# gpio4.net
KiCad netlist of a schematic drawn in EAGLE
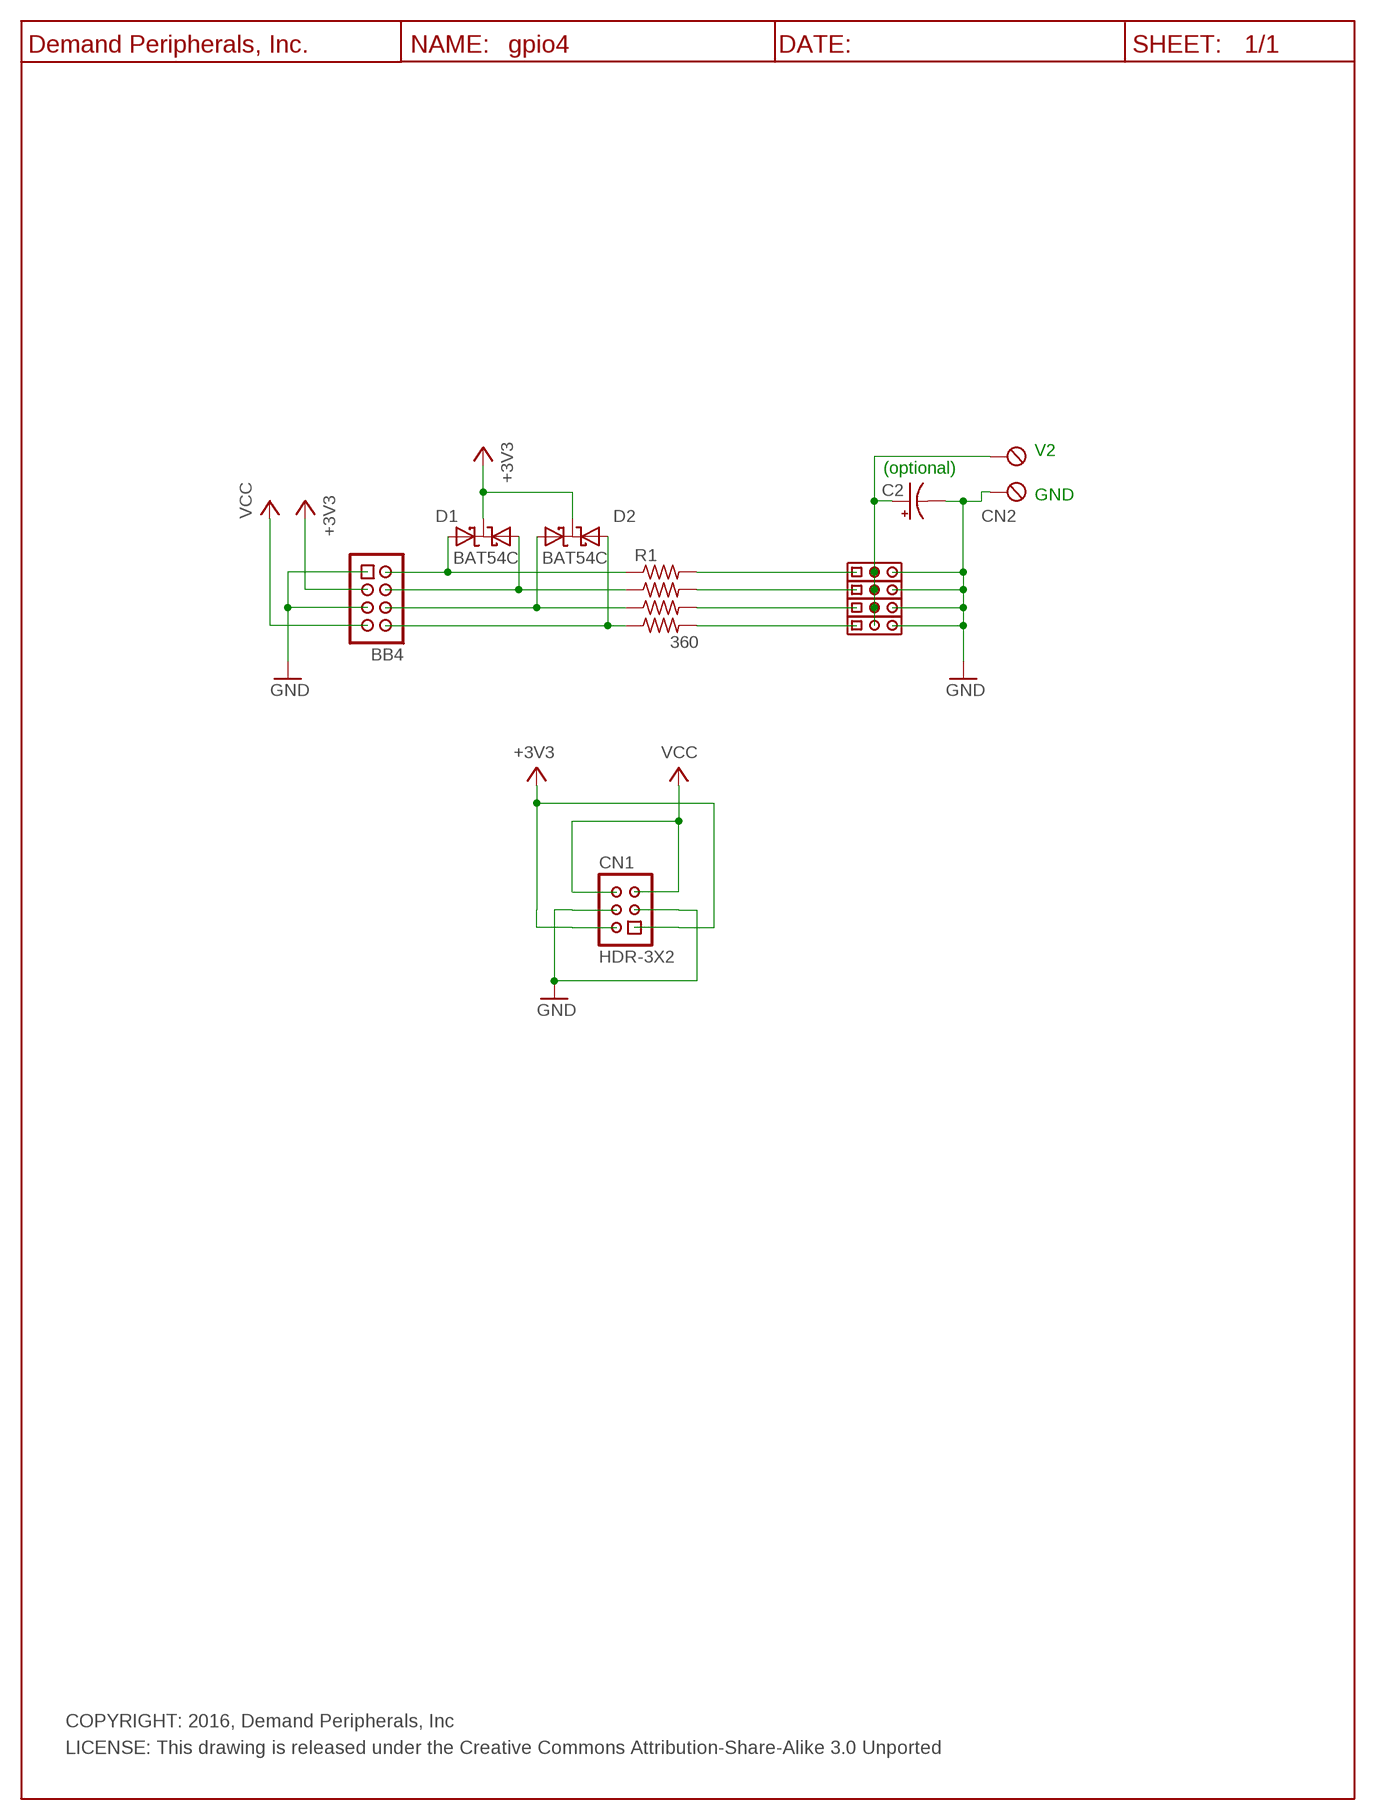
[diagram p0: schematic, sheet 1]

(export (version "E")
  (design (tool "Eeschema 10.0.6"))
  (components
    (comp (ref "BB4")
      (value "BB_CON")
      (footprint "eagle-import:HDR-4X2")
      (libsource (lib "eagle-import") (part "HDR-4X2-SHR"))
    )
    (comp (ref "C2")
      (value "100uF")
      (footprint "eagle-import:E3.5-8")
      (libsource (lib "eagle-import") (part "C100UF_E3.5-8"))
    )
    (comp (ref "CN1")
      (value "HDR-3X2")
      (footprint "eagle-import:HDR-3X2")
      (libsource (lib "eagle-import") (part "HDR-3X2"))
    )
    (comp (ref "CN2")
      (value "TBLK-5.08-X2")
      (footprint "eagle-import:TBLK-5.08-X2")
      (libsource (lib "eagle-import") (part "TBLK-5.08-X2"))
    )
    (comp (ref "D1")
      (value "BAT54C")
      (footprint "eagle-import:SOT23")
      (libsource (lib "eagle-import") (part "BAT54C"))
    )
    (comp (ref "D2")
      (value "BAT54C")
      (footprint "eagle-import:SOT23")
      (libsource (lib "eagle-import") (part "BAT54C"))
    )
    (comp (ref "R1")
      (value "360")
      (footprint "eagle-import:R0603")
      (libsource (lib "eagle-import") (part "R360_R0603"))
    )
    (comp (ref "R2")
      (value "360")
      (footprint "eagle-import:R0603")
      (libsource (lib "eagle-import") (part "R360_R0603"))
    )
    (comp (ref "R3")
      (value "360")
      (footprint "eagle-import:R0603")
      (libsource (lib "eagle-import") (part "R360_R0603"))
    )
    (comp (ref "R4")
      (value "360")
      (footprint "eagle-import:R0603")
      (libsource (lib "eagle-import") (part "R360_R0603"))
    )
    (comp (ref "U$1")
      (value "DP_FRAME_P")
      (footprint "eagle-import:P_FRAME")
      (libsource (lib "eagle-import") (part "DP_FRAME_P"))
    )
    (comp (ref "U$5")
      (value "HDR-3X1")
      (footprint "eagle-import:HDR-3X1")
      (libsource (lib "eagle-import") (part "HDR-3X1"))
    )
    (comp (ref "U$6")
      (value "HDR-3X1")
      (footprint "eagle-import:HDR-3X1")
      (libsource (lib "eagle-import") (part "HDR-3X1"))
    )
    (comp (ref "U$7")
      (value "HDR-3X1")
      (footprint "eagle-import:HDR-3X1")
      (libsource (lib "eagle-import") (part "HDR-3X1"))
    )
    (comp (ref "U$9")
      (value "HDR-3X1")
      (footprint "eagle-import:HDR-3X1")
      (libsource (lib "eagle-import") (part "HDR-3X1"))
    )
  )
  (nets
    (net (code "1") (name "+3V3") (class "Default")
      (node (ref "BB4") (pin "3") (pinfunction "3_3") (pintype "passive"))
      (node (ref "CN1") (pin "1") (pinfunction "1_1") (pintype "passive"))
      (node (ref "CN1") (pin "2") (pinfunction "2_2") (pintype "passive"))
      (node (ref "D1") (pin "3") (pinfunction "CC_3") (pintype "passive"))
      (node (ref "D2") (pin "3") (pinfunction "CC_3") (pintype "passive"))
    )
    (net (code "2") (name "GND") (class "Default")
      (node (ref "BB4") (pin "1") (pinfunction "1_1") (pintype "passive"))
      (node (ref "BB4") (pin "5") (pinfunction "5_5") (pintype "passive"))
      (node (ref "C2") (pin "-") (pinfunction "-_-") (pintype "passive"))
      (node (ref "CN1") (pin "3") (pinfunction "3_3") (pintype "passive"))
      (node (ref "CN1") (pin "4") (pinfunction "4_4") (pintype "passive"))
      (node (ref "CN2") (pin "1") (pinfunction "KL_1") (pintype "passive"))
      (node (ref "U$5") (pin "3") (pinfunction "3_3") (pintype "passive"))
      (node (ref "U$6") (pin "3") (pinfunction "3_3") (pintype "passive"))
      (node (ref "U$7") (pin "3") (pinfunction "3_3") (pintype "passive"))
      (node (ref "U$9") (pin "3") (pinfunction "3_3") (pintype "passive"))
    )
    (net (code "3") (name "Net-(CN2-KL1)") (class "Default")
      (node (ref "C2") (pin "+") (pinfunction "+_+") (pintype "passive"))
      (node (ref "CN2") (pin "2") (pinfunction "KL1_2") (pintype "passive"))
      (node (ref "U$5") (pin "2") (pinfunction "2_2") (pintype "passive"))
      (node (ref "U$6") (pin "2") (pinfunction "2_2") (pintype "passive"))
      (node (ref "U$7") (pin "2") (pinfunction "2_2") (pintype "passive"))
      (node (ref "U$9") (pin "2") (pinfunction "2_2") (pintype "passive"))
    )
    (net (code "4") (name "Net-(D1-A)") (class "Default")
      (node (ref "BB4") (pin "4") (pinfunction "4_4") (pintype "passive"))
      (node (ref "D1") (pin "2") (pinfunction "A_2") (pintype "passive"))
      (node (ref "R2") (pin "1") (pinfunction "1_1") (pintype "passive"))
    )
    (net (code "5") (name "Net-(D1-A1)") (class "Default")
      (node (ref "BB4") (pin "2") (pinfunction "2_2") (pintype "passive"))
      (node (ref "D1") (pin "1") (pinfunction "A1_1") (pintype "passive"))
      (node (ref "R1") (pin "1") (pinfunction "1_1") (pintype "passive"))
    )
    (net (code "6") (name "Net-(D2-A)") (class "Default")
      (node (ref "BB4") (pin "8") (pinfunction "8_8") (pintype "passive"))
      (node (ref "D2") (pin "2") (pinfunction "A_2") (pintype "passive"))
      (node (ref "R4") (pin "1") (pinfunction "1_1") (pintype "passive"))
    )
    (net (code "7") (name "Net-(D2-A1)") (class "Default")
      (node (ref "BB4") (pin "6") (pinfunction "6_6") (pintype "passive"))
      (node (ref "D2") (pin "1") (pinfunction "A1_1") (pintype "passive"))
      (node (ref "R3") (pin "1") (pinfunction "1_1") (pintype "passive"))
    )
    (net (code "8") (name "Net-(R1-Pad2)") (class "Default")
      (node (ref "R1") (pin "2") (pinfunction "2_2") (pintype "passive"))
      (node (ref "U$5") (pin "1") (pinfunction "1_1") (pintype "passive"))
    )
    (net (code "9") (name "Net-(R2-Pad2)") (class "Default")
      (node (ref "R2") (pin "2") (pinfunction "2_2") (pintype "passive"))
      (node (ref "U$6") (pin "1") (pinfunction "1_1") (pintype "passive"))
    )
    (net (code "10") (name "Net-(R3-Pad2)") (class "Default")
      (node (ref "R3") (pin "2") (pinfunction "2_2") (pintype "passive"))
      (node (ref "U$7") (pin "1") (pinfunction "1_1") (pintype "passive"))
    )
    (net (code "11") (name "Net-(R4-Pad2)") (class "Default")
      (node (ref "R4") (pin "2") (pinfunction "2_2") (pintype "passive"))
      (node (ref "U$9") (pin "1") (pinfunction "1_1") (pintype "passive"))
    )
    (net (code "12") (name "VCC") (class "Default")
      (node (ref "BB4") (pin "7") (pinfunction "7_7") (pintype "passive"))
      (node (ref "CN1") (pin "5") (pinfunction "5_5") (pintype "passive"))
      (node (ref "CN1") (pin "6") (pinfunction "6_6") (pintype "passive"))
    )
  )
)
